# 13-Power-P3V3.net
KiCad netlist of a schematic drawn in Altium Designer
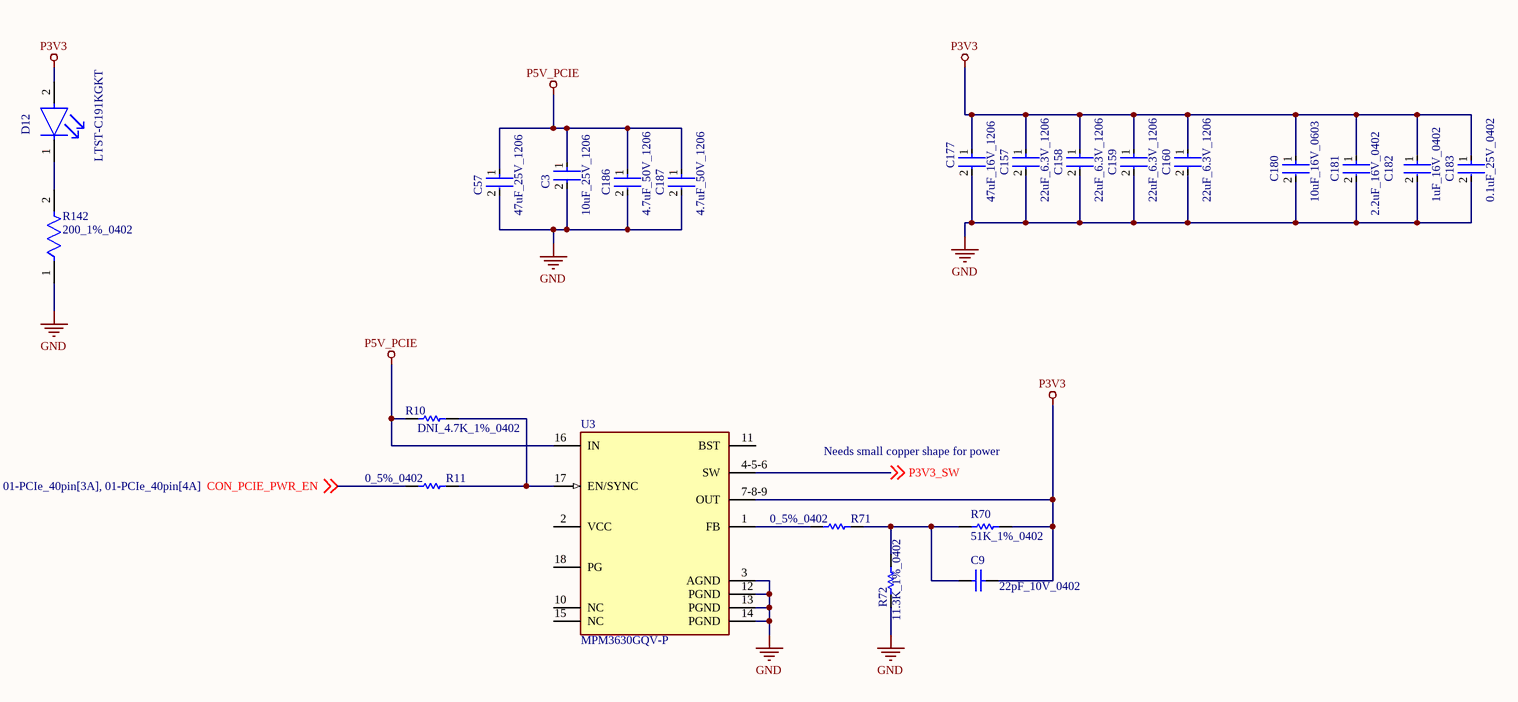
[diagram p0: 13-Power-P3V3.SchDoc]

(export (version "E")
  (design (tool "Eeschema 10.0.6"))
  (components
    (comp (ref "C3")
      (value "10uF_25V_1206")
      (footprint "FP-1206-L_3_2_0_2-W_1_6_0-IPC_A")
      (description "General Purpose Ceramic Capacitor, 1206, 10uF, 20%, X5R, 15%, 25V")
      (fields (field (name "TOLERANCE") "20%"))
      (libsource (lib "Altium Content Vault") (part "02cd4be3c70576c341d710602a673aa"))
    )
    (comp (ref "C9")
      (value "22pF_10V_0402")
      (footprint "CAPC1005X56X25LL10T15")
      (fields
        (field (name "PART NUMBER") "0402ZA220JAT2A")
        (field (name "MANUFACTURER") "AVX Interconnect / Elco")
      )
      (libsource (lib "Altium Content Vault") (part "CAP"))
    )
    (comp (ref "C57")
      (value "47uF_25V_1206")
      (footprint "FP-C3216-160-0_2-MFG")
      (description "Multilayer Ceramic Capacitors 47uF ±20% 25V X5R SMD 1206")
      (fields (field (name "VOLTAGE") "25V") (field (name "TOLERANCE") "20%"))
      (libsource (lib "Altium Content Vault") (part "11868f565c42a9108669ba33697ecf6"))
    )
    (comp (ref "C157")
      (value "22uF_6.3V_1206")
      (footprint "FP-1206-L_3_2_0_2-W_1_6_0-IPC_C")
      (description "General Purpose Ceramic Capacitor, 1206, 22uF, 20%, X5R, 15%, 6.3V")
      (fields (field (name "TOLERANCE") "20%") (field (name "VOLTAGE") "6.3V"))
      (libsource (lib "Altium Content Vault") (part "02cd4be3c70576c341d710602a673aa"))
    )
    (comp (ref "C158")
      (value "22uF_6.3V_1206")
      (footprint "FP-1206-L_3_2_0_2-W_1_6_0-IPC_C")
      (description "General Purpose Ceramic Capacitor, 1206, 22uF, 20%, X5R, 15%, 6.3V")
      (fields (field (name "TOLERANCE") "20%") (field (name "VOLTAGE") "6.3V"))
      (libsource (lib "Altium Content Vault") (part "02cd4be3c70576c341d710602a673aa"))
    )
    (comp (ref "C159")
      (value "22uF_6.3V_1206")
      (footprint "FP-1206-L_3_2_0_2-W_1_6_0-IPC_C")
      (description "General Purpose Ceramic Capacitor, 1206, 22uF, 20%, X5R, 15%, 6.3V")
      (fields (field (name "TOLERANCE") "20%") (field (name "VOLTAGE") "6.3V"))
      (libsource (lib "Altium Content Vault") (part "02cd4be3c70576c341d710602a673aa"))
    )
    (comp (ref "C160")
      (value "22uF_6.3V_1206")
      (footprint "FP-1206-L_3_2_0_2-W_1_6_0-IPC_C")
      (description "General Purpose Ceramic Capacitor, 1206, 22uF, 20%, X5R, 15%, 6.3V")
      (fields (field (name "TOLERANCE") "20%") (field (name "VOLTAGE") "6.3V"))
      (libsource (lib "Altium Content Vault") (part "02cd4be3c70576c341d710602a673aa"))
    )
    (comp (ref "C177")
      (value "47uF_16V_1206")
      (footprint "FP-C3216-160-0_2-MFG")
      (description "Multilayer Ceramic Capacitors 47uF ±20% 16V X5R SMD 1206")
      (fields (field (name "TOLERANCE") "20%"))
      (libsource (lib "Altium Content Vault") (part "11868f565c42a9108669ba33697ecf6"))
    )
    (comp (ref "C180")
      (value "10uF_16V_0603")
      (footprint "FP-0603-L_1_6_0_2-W_0_8_0-MFG")
      (description "Multilayer Ceramic Capacitor 10uF 16V X5R 20% SMD 0603 T/R")
      (fields (field (name "TOLERANCE") "20%"))
      (libsource (lib "Altium Content Vault") (part "b4654b650e69147ec39a6b967a45e02"))
    )
    (comp (ref "C181")
      (value "2.2uF_16V_0402")
      (footprint "FP-C1005-050-0_05-IPC_A")
      (description "Multilayer Ceramic Capacitors 2.2μF ±10% 16V X5R SMD 0402")
      (fields (field (name "TOLERANCE") "10%"))
      (libsource (lib "Altium Content Vault") (part "b4654b650e69147ec39a6b967a45e02"))
    )
    (comp (ref "C182")
      (value "1uF_16V_0402")
      (footprint "FP-0402-L_1_0_0_05-W_0_5-IPC_A")
      (description "None")
      (fields (field (name "TOLERANCE") "10%"))
      (libsource (lib "Altium Content Vault") (part "b4654b650e69147ec39a6b967a45e02"))
    )
    (comp (ref "C183")
      (value "0.1uF_25V_0402")
      (footprint "FP-0402-L_1_0_1-W_0_5_0_1-IPC_C")
      (description "General Purpose Ceramic Capacitor, 0402, 100nF, 10%, X7R, 15%, 25V")
      (fields (field (name "VOLTAGE") "25V") (field (name "TOLERANCE") "10%"))
      (libsource (lib "Altium Content Vault") (part "b4654b650e69147ec39a6b967a45e02"))
    )
    (comp (ref "C186")
      (value "4.7uF_50V_1206")
      (footprint "FP-GRM31C-0_2-e0_3_0_8-IPC_C")
      (description "Chip Multilayer Ceramic Capacitors for General Purpose, 1206, 4.7uF, X7R, 15%, 10%, 50V")
      (fields (field (name "VOLTAGE") "50V") (field (name "TOLERANCE") "10%"))
      (libsource (lib "Altium Content Vault") (part "02cd4be3c70576c341d710602a673aa"))
    )
    (comp (ref "C187")
      (value "4.7uF_50V_1206")
      (footprint "FP-GRM31C-0_2-e0_3_0_8-IPC_C")
      (description "Chip Multilayer Ceramic Capacitors for General Purpose, 1206, 4.7uF, X7R, 15%, 10%, 50V")
      (fields (field (name "VOLTAGE") "50V") (field (name "TOLERANCE") "10%"))
      (libsource (lib "Altium Content Vault") (part "02cd4be3c70576c341d710602a673aa"))
    )
    (comp (ref "D12")
      (value "LTST-C191KGKT")
      (footprint "FP-LTST-C191KGKT-MFG")
      (description "LED GREEN CLEAR SMD")
      (libsource (lib "Altium Content Vault") (part "8706943c75ba83719d021d2fdc84c58"))
    )
    (comp (ref "R10")
      (value "DNI_4.7K_1%_0402")
      (footprint "RESC1005X40X25NL10T10")
      (fields (field (name "MANUFACTURER") "Bourns") (field (name "PART NUMBER") "CR0402-FX-4701GLF"))
      (libsource (lib "Altium Content Vault") (part "RES"))
    )
    (comp (ref "R11")
      (value "0_5%_0402")
      (footprint "RESC1005X40X25LL10T10")
      (fields (field (name "MANUFACTURER") "KOA Speer") (field (name "PART NUMBER") "RK73Z1ETTP"))
      (libsource (lib "Altium Content Vault") (part "RES"))
    )
    (comp (ref "R70")
      (value "51K_1%_0402")
      (footprint "RESC1005X40X25ML10T10")
      (fields (field (name "MANUFACTURER") "KOA Speer") (field (name "PART NUMBER") "RK73H1ETTP5102F"))
      (libsource (lib "Altium Content Vault") (part "RES"))
    )
    (comp (ref "R71")
      (value "0_5%_0402")
      (footprint "RESC1005X40X25LL10T10")
      (fields (field (name "MANUFACTURER") "KOA Speer") (field (name "PART NUMBER") "RK73Z1ETTP"))
      (libsource (lib "Altium Content Vault") (part "RES"))
    )
    (comp (ref "R72")
      (value "11.3K_1%_0402")
      (footprint "RESC1005X40X25LL10T10")
      (fields (field (name "PART NUMBER") "RK73H1ETTP1132F") (field (name "MANUFACTURER") "KOA Speer"))
      (libsource (lib "Altium Content Vault") (part "RES"))
    )
    (comp (ref "R142")
      (value "200_1%_0402")
      (footprint "FP-ERJ2RK-IPC_A")
      (description "RES SMD 200 OHM 1% 1/10W 0402")
      (fields (field (name "TOLERANCE") "1%"))
      (libsource (lib "Altium Content Vault") (part "1029c3af85768c4190bb7ad29bc67b5"))
    )
    (comp (ref "U3")
      (value "MPM3630GQV-P")
      (footprint "FP-MPM3630GQV-P-MFG")
      (description "DC DC CONVERTER 0.6-18V")
      (libsource (lib "Altium Content Vault") (part "05efdfb8ddb6440aeb6b678d8a8d5f8"))
    )
  )
  (nets
    (net (code "1") (name "CON_PCIE_PWR_EN") (class "Default")
      (node (ref "R11") (pin "1") (pinfunction "1_1") (pintype "passive"))
    )
    (net (code "2") (name "GND") (class "Default")
      (node (ref "C157") (pin "2") (pinfunction "2_2") (pintype "passive"))
      (node (ref "C158") (pin "2") (pinfunction "2_2") (pintype "passive"))
      (node (ref "C159") (pin "2") (pinfunction "2_2") (pintype "passive"))
      (node (ref "C160") (pin "2") (pinfunction "2_2") (pintype "passive"))
      (node (ref "C177") (pin "2") (pinfunction "2_2") (pintype "passive"))
      (node (ref "C180") (pin "2") (pinfunction "2_2") (pintype "passive"))
      (node (ref "C181") (pin "2") (pinfunction "2_2") (pintype "passive"))
      (node (ref "C182") (pin "2") (pinfunction "2_2") (pintype "passive"))
      (node (ref "C183") (pin "2") (pinfunction "2_2") (pintype "passive"))
      (node (ref "C186") (pin "2") (pinfunction "2_2") (pintype "passive"))
      (node (ref "C187") (pin "2") (pinfunction "2_2") (pintype "passive"))
      (node (ref "C3") (pin "2") (pinfunction "2_2") (pintype "passive"))
      (node (ref "C57") (pin "2") (pinfunction "2_2") (pintype "passive"))
      (node (ref "R142") (pin "1") (pinfunction "1_1") (pintype "passive"))
      (node (ref "R72") (pin "2") (pinfunction "2_2") (pintype "passive"))
      (node (ref "U3") (pin "12") (pinfunction "PGND_12") (pintype "power_in"))
      (node (ref "U3") (pin "13") (pinfunction "PGND_13") (pintype "power_in"))
      (node (ref "U3") (pin "14") (pinfunction "PGND_14") (pintype "power_in"))
      (node (ref "U3") (pin "3") (pinfunction "AGND_3") (pintype "power_in"))
    )
    (net (code "3") (name "Net-(C9-Pad1)") (class "Default")
      (node (ref "C9") (pin "1") (pinfunction "1_1") (pintype "passive"))
      (node (ref "R70") (pin "1") (pinfunction "1_1") (pintype "passive"))
      (node (ref "R71") (pin "2") (pinfunction "2_2") (pintype "passive"))
      (node (ref "R72") (pin "1") (pinfunction "1_1") (pintype "passive"))
    )
    (net (code "4") (name "Net-(D12-C)") (class "Default")
      (node (ref "D12") (pin "1") (pinfunction "C_1") (pintype "passive"))
      (node (ref "R142") (pin "2") (pinfunction "2_2") (pintype "passive"))
    )
    (net (code "5") (name "Net-(U3-EN{slash}SYNC)") (class "Default")
      (node (ref "R10") (pin "2") (pinfunction "2_2") (pintype "passive"))
      (node (ref "R11") (pin "2") (pinfunction "2_2") (pintype "passive"))
      (node (ref "U3") (pin "17") (pinfunction "EN/SYNC_17") (pintype "input"))
    )
    (net (code "6") (name "Net-(U3-FB)") (class "Default")
      (node (ref "R71") (pin "1") (pinfunction "1_1") (pintype "passive"))
      (node (ref "U3") (pin "1") (pinfunction "FB_1") (pintype "passive"))
    )
    (net (code "7") (name "P3V3") (class "Default")
      (node (ref "C157") (pin "1") (pinfunction "1_1") (pintype "passive"))
      (node (ref "C158") (pin "1") (pinfunction "1_1") (pintype "passive"))
      (node (ref "C159") (pin "1") (pinfunction "1_1") (pintype "passive"))
      (node (ref "C160") (pin "1") (pinfunction "1_1") (pintype "passive"))
      (node (ref "C177") (pin "1") (pinfunction "1_1") (pintype "passive"))
      (node (ref "C180") (pin "1") (pinfunction "1_1") (pintype "passive"))
      (node (ref "C181") (pin "1") (pinfunction "1_1") (pintype "passive"))
      (node (ref "C182") (pin "1") (pinfunction "1_1") (pintype "passive"))
      (node (ref "C183") (pin "1") (pinfunction "1_1") (pintype "passive"))
      (node (ref "C9") (pin "2") (pinfunction "2_2") (pintype "passive"))
      (node (ref "D12") (pin "2") (pinfunction "A_2") (pintype "passive"))
      (node (ref "R70") (pin "2") (pinfunction "2_2") (pintype "passive"))
      (node (ref "U3") (pin "7-8-9") (pinfunction "OUT_7-8-9") (pintype "power_in"))
    )
    (net (code "8") (name "P3V3_SW") (class "Default")
      (node (ref "U3") (pin "4-5-6") (pinfunction "SW_4-5-6") (pintype "passive"))
    )
    (net (code "9") (name "P5V_PCIE") (class "Default")
      (node (ref "C186") (pin "1") (pinfunction "1_1") (pintype "passive"))
      (node (ref "C187") (pin "1") (pinfunction "1_1") (pintype "passive"))
      (node (ref "C3") (pin "1") (pinfunction "1_1") (pintype "passive"))
      (node (ref "C57") (pin "1") (pinfunction "1_1") (pintype "passive"))
      (node (ref "R10") (pin "1") (pinfunction "1_1") (pintype "passive"))
      (node (ref "U3") (pin "16") (pinfunction "IN_16") (pintype "power_in"))
    )
    (net (code "10") (name "unconnected-(U3-BST-Pad11)") (class "Default")
      (node (ref "U3") (pin "11") (pinfunction "BST_11") (pintype "passive"))
    )
    (net (code "11") (name "unconnected-(U3-NC-Pad10)") (class "Default")
      (node (ref "U3") (pin "10") (pinfunction "NC_10") (pintype "passive"))
    )
    (net (code "12") (name "unconnected-(U3-NC-Pad15)") (class "Default")
      (node (ref "U3") (pin "15") (pinfunction "NC_15") (pintype "passive"))
    )
    (net (code "13") (name "unconnected-(U3-PG-Pad18)") (class "Default")
      (node (ref "U3") (pin "18") (pinfunction "PG_18") (pintype "open_collector"))
    )
    (net (code "14") (name "unconnected-(U3-VCC-Pad2)") (class "Default")
      (node (ref "U3") (pin "2") (pinfunction "VCC_2") (pintype "passive"))
    )
  )
)
